# 4_PushButtons.net
KiCad netlist of a schematic drawn in Altium Designer
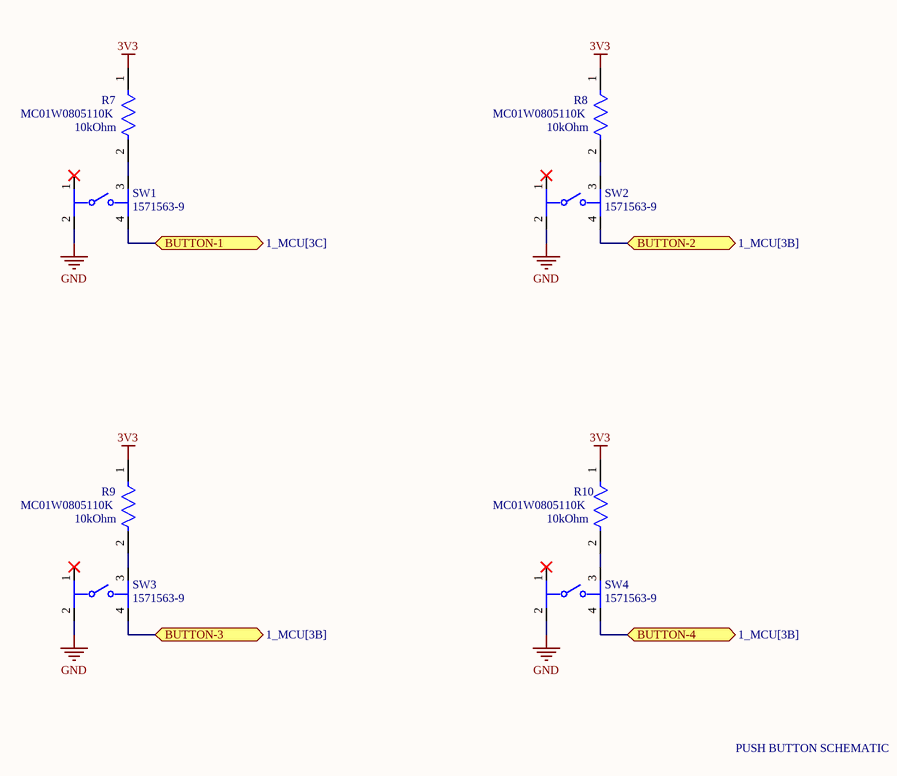
[diagram p0: 4_PushButtons.SchDoc]

(export (version "E")
  (design (tool "Eeschema 10.0.6"))
  (components
    (comp (ref "R7")
      (value "MC01W0805110K")
      (footprint "FP-MC01W0805-IPC_C")
      (description "Resistor, 10K, 0.1W, 1%, 0805, Reel")
      (fields (field (name "TOLERANCE") "1%"))
      (libsource (lib "Altium Content Vault") (part "1029c3af85768c4190bb7ad29bc67b5"))
    )
    (comp (ref "R8")
      (value "MC01W0805110K")
      (footprint "FP-MC01W0805-IPC_C")
      (description "Resistor, 10K, 0.1W, 1%, 0805, Reel")
      (fields (field (name "TOLERANCE") "1%"))
      (libsource (lib "Altium Content Vault") (part "1029c3af85768c4190bb7ad29bc67b5"))
    )
    (comp (ref "R9")
      (value "MC01W0805110K")
      (footprint "FP-MC01W0805-IPC_C")
      (description "Resistor, 10K, 0.1W, 1%, 0805, Reel")
      (fields (field (name "TOLERANCE") "1%"))
      (libsource (lib "Altium Content Vault") (part "1029c3af85768c4190bb7ad29bc67b5"))
    )
    (comp (ref "R10")
      (value "MC01W0805110K")
      (footprint "FP-MC01W0805-IPC_C")
      (description "Resistor, 10K, 0.1W, 1%, 0805, Reel")
      (fields (field (name "TOLERANCE") "1%"))
      (libsource (lib "Altium Content Vault") (part "1029c3af85768c4190bb7ad29bc67b5"))
    )
    (comp (ref "SW1")
      (value "1571563-9")
      (footprint "FP-1571563-9-MFG")
      (description "SWITCH TACTILE SPST-NO 0.05A 24V")
      (fields
        (field (name "MANUFACTURER") "TE Connectivity")
        (field (name "OCTOPART") "https://octopart.com/1571563-9-te+connectivity-41253969")
      )
      (libsource (lib "Altium Content Vault") (part "b8895f3f4cefb76e1819d2863dba89b"))
    )
    (comp (ref "SW2")
      (value "1571563-9")
      (footprint "FP-1571563-9-MFG")
      (description "SWITCH TACTILE SPST-NO 0.05A 24V")
      (fields
        (field (name "MANUFACTURER") "TE Connectivity")
        (field (name "OCTOPART") "https://octopart.com/1571563-9-te+connectivity-41253969")
      )
      (libsource (lib "Altium Content Vault") (part "b8895f3f4cefb76e1819d2863dba89b"))
    )
    (comp (ref "SW3")
      (value "1571563-9")
      (footprint "FP-1571563-9-MFG")
      (description "SWITCH TACTILE SPST-NO 0.05A 24V")
      (fields
        (field (name "MANUFACTURER") "TE Connectivity")
        (field (name "OCTOPART") "https://octopart.com/1571563-9-te+connectivity-41253969")
      )
      (libsource (lib "Altium Content Vault") (part "b8895f3f4cefb76e1819d2863dba89b"))
    )
    (comp (ref "SW4")
      (value "1571563-9")
      (footprint "FP-1571563-9-MFG")
      (description "SWITCH TACTILE SPST-NO 0.05A 24V")
      (fields
        (field (name "MANUFACTURER") "TE Connectivity")
        (field (name "OCTOPART") "https://octopart.com/1571563-9-te+connectivity-41253969")
      )
      (libsource (lib "Altium Content Vault") (part "b8895f3f4cefb76e1819d2863dba89b"))
    )
  )
  (nets
    (net (code "1") (name "/BUTTON-1") (class "Default")
      (node (ref "SW1") (pin "4") (pinfunction "4_4") (pintype "passive"))
    )
    (net (code "2") (name "/BUTTON-2") (class "Default")
      (node (ref "SW2") (pin "4") (pinfunction "4_4") (pintype "passive"))
    )
    (net (code "3") (name "/BUTTON-3") (class "Default")
      (node (ref "SW3") (pin "4") (pinfunction "4_4") (pintype "passive"))
    )
    (net (code "4") (name "/BUTTON-4") (class "Default")
      (node (ref "SW4") (pin "4") (pinfunction "4_4") (pintype "passive"))
    )
    (net (code "5") (name "3V3") (class "Default")
      (node (ref "R10") (pin "1") (pinfunction "1_1") (pintype "passive"))
      (node (ref "R7") (pin "1") (pinfunction "1_1") (pintype "passive"))
      (node (ref "R8") (pin "1") (pinfunction "1_1") (pintype "passive"))
      (node (ref "R9") (pin "1") (pinfunction "1_1") (pintype "passive"))
    )
    (net (code "6") (name "GND") (class "Default")
      (node (ref "SW1") (pin "2") (pinfunction "2_2") (pintype "passive"))
      (node (ref "SW2") (pin "2") (pinfunction "2_2") (pintype "passive"))
      (node (ref "SW3") (pin "2") (pinfunction "2_2") (pintype "passive"))
      (node (ref "SW4") (pin "2") (pinfunction "2_2") (pintype "passive"))
    )
    (net (code "7") (name "Net-(R7-Pad2)") (class "Default")
      (node (ref "R7") (pin "2") (pinfunction "2_2") (pintype "passive"))
      (node (ref "SW1") (pin "3") (pinfunction "3_3") (pintype "passive"))
    )
    (net (code "8") (name "Net-(R8-Pad2)") (class "Default")
      (node (ref "R8") (pin "2") (pinfunction "2_2") (pintype "passive"))
      (node (ref "SW2") (pin "3") (pinfunction "3_3") (pintype "passive"))
    )
    (net (code "9") (name "Net-(R9-Pad2)") (class "Default")
      (node (ref "R9") (pin "2") (pinfunction "2_2") (pintype "passive"))
      (node (ref "SW3") (pin "3") (pinfunction "3_3") (pintype "passive"))
    )
    (net (code "10") (name "Net-(R10-Pad2)") (class "Default")
      (node (ref "R10") (pin "2") (pinfunction "2_2") (pintype "passive"))
      (node (ref "SW4") (pin "3") (pinfunction "3_3") (pintype "passive"))
    )
    (net (code "11") (name "unconnected-(SW1-Pad1)") (class "Default")
      (node (ref "SW1") (pin "1") (pinfunction "1_1") (pintype "passive+no_connect"))
    )
    (net (code "12") (name "unconnected-(SW2-Pad1)") (class "Default")
      (node (ref "SW2") (pin "1") (pinfunction "1_1") (pintype "passive+no_connect"))
    )
    (net (code "13") (name "unconnected-(SW3-Pad1)") (class "Default")
      (node (ref "SW3") (pin "1") (pinfunction "1_1") (pintype "passive+no_connect"))
    )
    (net (code "14") (name "unconnected-(SW4-Pad1)") (class "Default")
      (node (ref "SW4") (pin "1") (pinfunction "1_1") (pintype "passive+no_connect"))
    )
  )
)
